# aecho.net
KiCad netlist of a schematic drawn in EAGLE
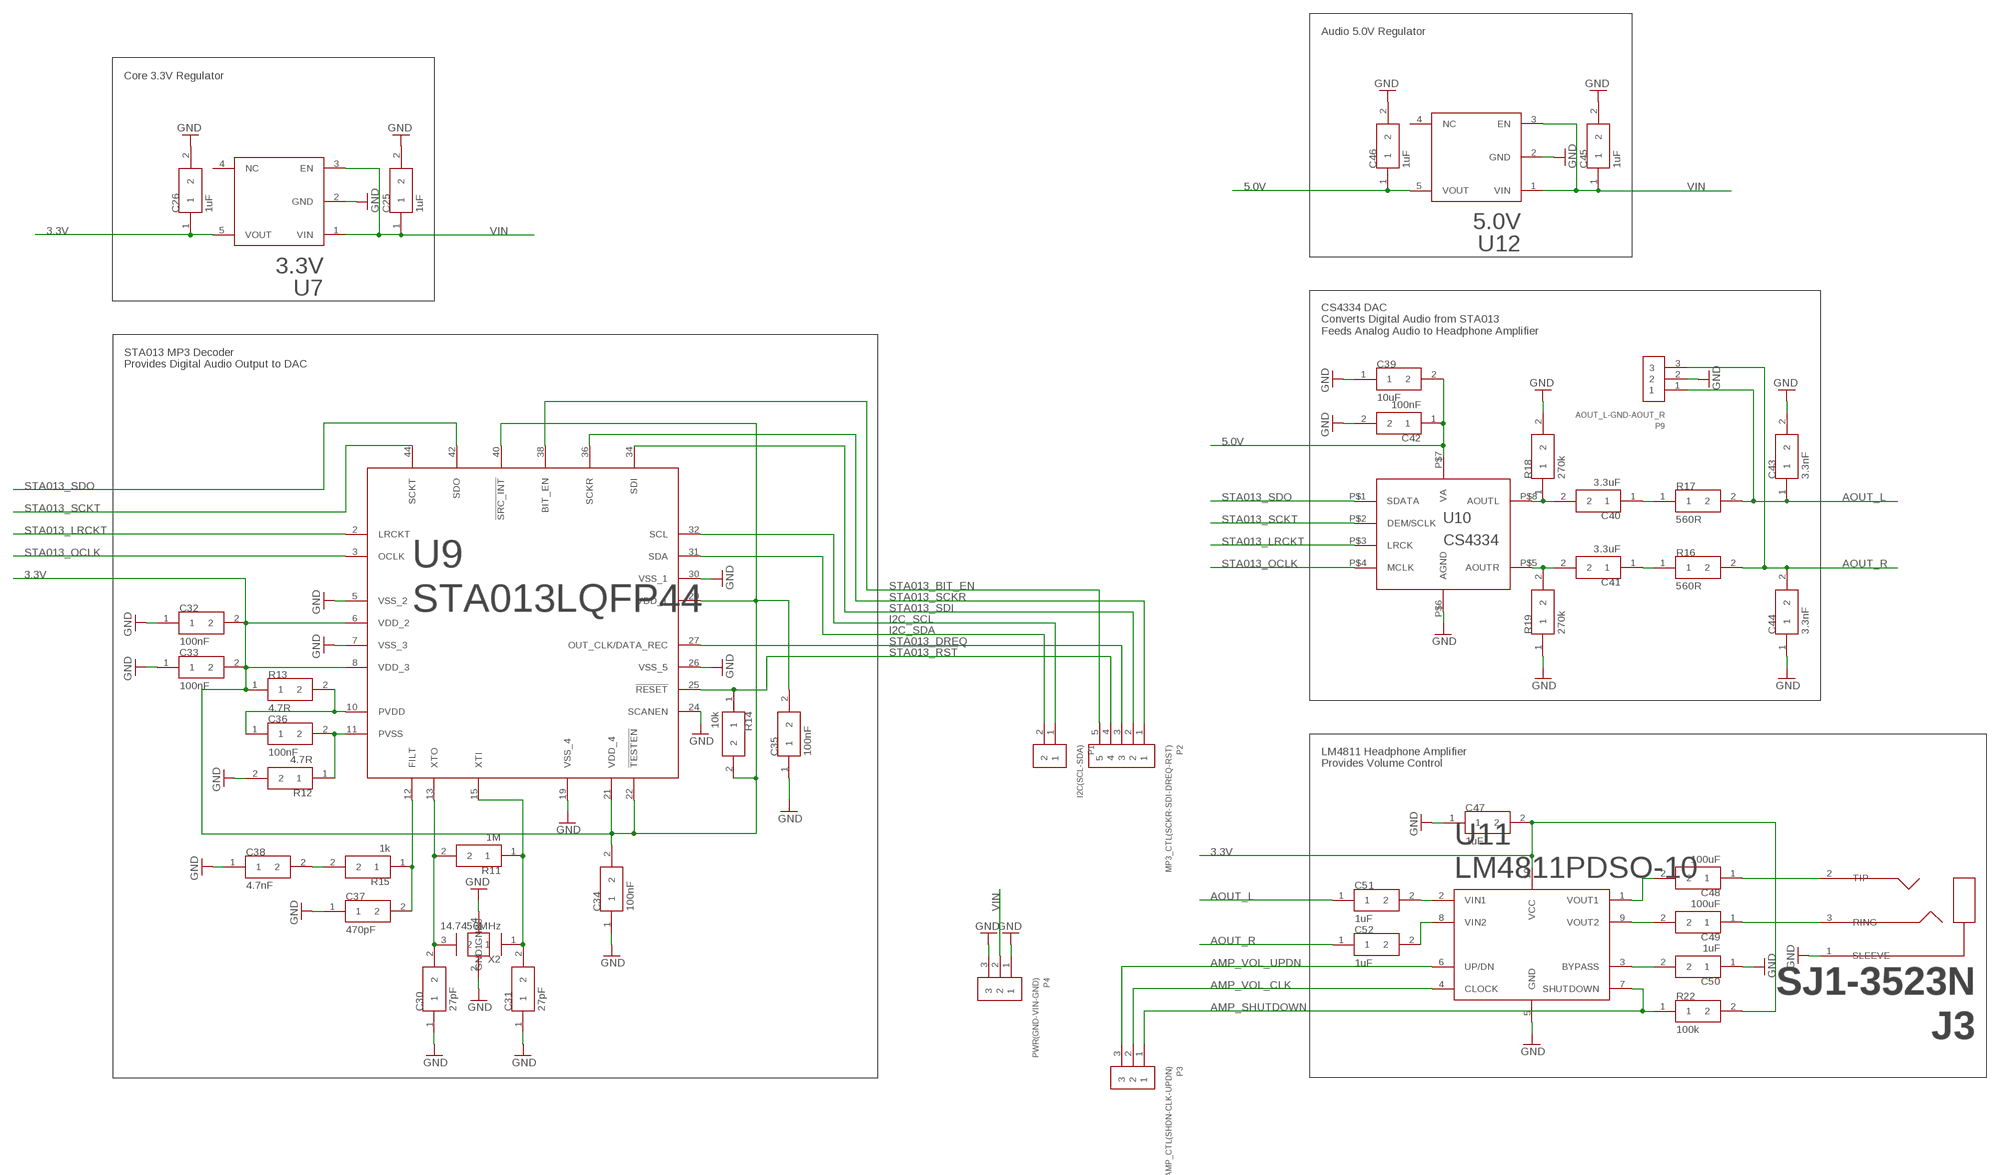
[diagram p0: schematic, sheet 1]

(export (version "E")
  (design (tool "Eeschema 10.0.6"))
  (components
    (comp (ref "C25")
      (value "1uF")
      (footprint "eagle-import:0805")
      (libsource (lib "eagle-import") (part "CAP0805"))
    )
    (comp (ref "C26")
      (value "1uF")
      (footprint "eagle-import:0805")
      (libsource (lib "eagle-import") (part "CAP0805"))
    )
    (comp (ref "C30")
      (value "27pF")
      (footprint "eagle-import:0805")
      (libsource (lib "eagle-import") (part "CAP0805"))
    )
    (comp (ref "C31")
      (value "27pF")
      (footprint "eagle-import:0805")
      (libsource (lib "eagle-import") (part "CAP0805"))
    )
    (comp (ref "C32")
      (value "100nF")
      (footprint "eagle-import:0805")
      (libsource (lib "eagle-import") (part "CAP0805"))
    )
    (comp (ref "C33")
      (value "100nF")
      (footprint "eagle-import:0805")
      (libsource (lib "eagle-import") (part "CAP0805"))
    )
    (comp (ref "C34")
      (value "100nF")
      (footprint "eagle-import:0805")
      (libsource (lib "eagle-import") (part "CAP0805"))
    )
    (comp (ref "C35")
      (value "100nF")
      (footprint "eagle-import:0805")
      (libsource (lib "eagle-import") (part "CAP0805"))
    )
    (comp (ref "C36")
      (value "100nF")
      (footprint "eagle-import:0805")
      (libsource (lib "eagle-import") (part "CAP0805"))
    )
    (comp (ref "C37")
      (value "470pF")
      (footprint "eagle-import:0805")
      (libsource (lib "eagle-import") (part "CAP0805"))
    )
    (comp (ref "C38")
      (value "4.7nF")
      (footprint "eagle-import:0805")
      (libsource (lib "eagle-import") (part "CAP0805"))
    )
    (comp (ref "C39")
      (value "10uF")
      (footprint "eagle-import:0805")
      (libsource (lib "eagle-import") (part "CAP0805"))
    )
    (comp (ref "C40")
      (value "3.3uF")
      (footprint "eagle-import:0805")
      (libsource (lib "eagle-import") (part "CAP0805"))
    )
    (comp (ref "C41")
      (value "3.3uF")
      (footprint "eagle-import:0805")
      (libsource (lib "eagle-import") (part "CAP0805"))
    )
    (comp (ref "C42")
      (value "100nF")
      (footprint "eagle-import:0805")
      (libsource (lib "eagle-import") (part "CAP0805"))
    )
    (comp (ref "C43")
      (value "3.3nF")
      (footprint "eagle-import:0805")
      (libsource (lib "eagle-import") (part "CAP0805"))
    )
    (comp (ref "C44")
      (value "3.3nF")
      (footprint "eagle-import:0805")
      (libsource (lib "eagle-import") (part "CAP0805"))
    )
    (comp (ref "C45")
      (value "1uF")
      (footprint "eagle-import:0805")
      (libsource (lib "eagle-import") (part "CAP0805"))
    )
    (comp (ref "C46")
      (value "1uF")
      (footprint "eagle-import:0805")
      (libsource (lib "eagle-import") (part "CAP0805"))
    )
    (comp (ref "C47")
      (value "1uF")
      (footprint "eagle-import:0805")
      (libsource (lib "eagle-import") (part "CAP0805"))
    )
    (comp (ref "C48")
      (value "100uF")
      (footprint "eagle-import:1210")
      (libsource (lib "eagle-import") (part "CAP1210"))
    )
    (comp (ref "C49")
      (value "100uF")
      (footprint "eagle-import:1210")
      (libsource (lib "eagle-import") (part "CAP1210"))
    )
    (comp (ref "C50")
      (value "1uF")
      (footprint "eagle-import:0805")
      (libsource (lib "eagle-import") (part "CAP0805"))
    )
    (comp (ref "C51")
      (value "1uF")
      (footprint "eagle-import:0805")
      (libsource (lib "eagle-import") (part "CAP0805"))
    )
    (comp (ref "C52")
      (value "1uF")
      (footprint "eagle-import:0805")
      (libsource (lib "eagle-import") (part "CAP0805"))
    )
    (comp (ref "J3")
      (value "SJ1-3523N")
      (footprint "eagle-import:SJ1-352XN")
      (libsource (lib "eagle-import") (part "SJ1-3523N"))
    )
    (comp (ref "P1")
      (value "I2C(SCL-SDA)")
      (footprint "eagle-import:PIN_2")
      (libsource (lib "eagle-import") (part "PIN_2"))
    )
    (comp (ref "P2")
      (value "MP3_CTL(SCKR-SDI-DREQ-RST)")
      (footprint "eagle-import:PIN_5")
      (libsource (lib "eagle-import") (part "PIN_5"))
    )
    (comp (ref "P3")
      (value "AMP_CTL(SHDN-CLK-UPDN)")
      (footprint "eagle-import:PIN_3")
      (libsource (lib "eagle-import") (part "PIN_3"))
    )
    (comp (ref "P4")
      (value "PWR(GND-VIN-GND)")
      (footprint "eagle-import:PIN_3")
      (libsource (lib "eagle-import") (part "PIN_3"))
    )
    (comp (ref "P9")
      (value "AOUT_L-GND-AOUT_R")
      (footprint "eagle-import:PIN_3")
      (libsource (lib "eagle-import") (part "PIN_3"))
    )
    (comp (ref "R11")
      (value "1M")
      (footprint "eagle-import:0805")
      (libsource (lib "eagle-import") (part "RES0805"))
    )
    (comp (ref "R12")
      (value "4.7R")
      (footprint "eagle-import:0805")
      (libsource (lib "eagle-import") (part "RES0805"))
    )
    (comp (ref "R13")
      (value "4.7R")
      (footprint "eagle-import:0805")
      (libsource (lib "eagle-import") (part "RES0805"))
    )
    (comp (ref "R14")
      (value "10k")
      (footprint "eagle-import:0805")
      (libsource (lib "eagle-import") (part "RES0805"))
    )
    (comp (ref "R15")
      (value "1k")
      (footprint "eagle-import:0805")
      (libsource (lib "eagle-import") (part "RES0805"))
    )
    (comp (ref "R16")
      (value "560R")
      (footprint "eagle-import:0805")
      (libsource (lib "eagle-import") (part "RES0805"))
    )
    (comp (ref "R17")
      (value "560R")
      (footprint "eagle-import:0805")
      (libsource (lib "eagle-import") (part "RES0805"))
    )
    (comp (ref "R18")
      (value "270k")
      (footprint "eagle-import:0805")
      (libsource (lib "eagle-import") (part "RES0805"))
    )
    (comp (ref "R19")
      (value "270k")
      (footprint "eagle-import:0805")
      (libsource (lib "eagle-import") (part "RES0805"))
    )
    (comp (ref "R22")
      (value "100k")
      (footprint "eagle-import:0805")
      (libsource (lib "eagle-import") (part "RES0805"))
    )
    (comp (ref "U7")
      (value "3.3V")
      (footprint "eagle-import:SOT23-5")
      (libsource (lib "eagle-import") (part "LP3985SOT23-5"))
    )
    (comp (ref "U9")
      (value "STA013LQFP44")
      (footprint "eagle-import:QFP44")
      (libsource (lib "eagle-import") (part "STA013LQFP44"))
    )
    (comp (ref "U10")
      (value "CS4334")
      (footprint "eagle-import:SO8")
      (libsource (lib "eagle-import") (part "CS4334"))
    )
    (comp (ref "U11")
      (value "LM4811PDSO-10")
      (footprint "eagle-import:PDSO-10")
      (libsource (lib "eagle-import") (part "LM4811PDSO-10"))
    )
    (comp (ref "U12")
      (value "5.0V")
      (footprint "eagle-import:SOT23-5")
      (libsource (lib "eagle-import") (part "LP3985SOT23-5"))
    )
    (comp (ref "X2")
      (value "14.7456MHz")
      (footprint "eagle-import:XTAL_3225")
      (libsource (lib "eagle-import") (part "XTAL_GNDSMD_3225"))
    )
  )
  (nets
    (net (code "1") (name "/3.3V") (class "Default")
      (node (ref "C26") (pin "1") (pinfunction "1_1") (pintype "bidirectional"))
      (node (ref "C32") (pin "2") (pinfunction "2_2") (pintype "bidirectional"))
      (node (ref "C33") (pin "2") (pinfunction "2_2") (pintype "bidirectional"))
      (node (ref "C34") (pin "2") (pinfunction "2_2") (pintype "bidirectional"))
      (node (ref "C35") (pin "2") (pinfunction "2_2") (pintype "bidirectional"))
      (node (ref "C47") (pin "2") (pinfunction "2_2") (pintype "bidirectional"))
      (node (ref "R13") (pin "1") (pinfunction "1_1") (pintype "bidirectional"))
      (node (ref "R14") (pin "2") (pinfunction "2_2") (pintype "bidirectional"))
      (node (ref "R22") (pin "2") (pinfunction "2_2") (pintype "bidirectional"))
      (node (ref "U11") (pin "10") (pinfunction "VCC_10") (pintype "bidirectional"))
      (node (ref "U7") (pin "5") (pinfunction "VOUT_5") (pintype "bidirectional"))
      (node (ref "U9") (pin "21") (pinfunction "VDD_4_21") (pintype "bidirectional"))
      (node (ref "U9") (pin "22") (pinfunction "~{TESTEN}_22") (pintype "bidirectional"))
      (node (ref "U9") (pin "29") (pinfunction "VDD_1_29") (pintype "bidirectional"))
      (node (ref "U9") (pin "40") (pinfunction "~{SRC_INT}_40") (pintype "bidirectional"))
      (node (ref "U9") (pin "6") (pinfunction "VDD_2_6") (pintype "bidirectional"))
      (node (ref "U9") (pin "8") (pinfunction "VDD_3_8") (pintype "bidirectional"))
    )
    (net (code "2") (name "/5.0V") (class "Default")
      (node (ref "C39") (pin "2") (pinfunction "2_2") (pintype "bidirectional"))
      (node (ref "C42") (pin "1") (pinfunction "1_1") (pintype "bidirectional"))
      (node (ref "C46") (pin "1") (pinfunction "1_1") (pintype "bidirectional"))
      (node (ref "U10") (pin "P$7") (pinfunction "VA_P$7") (pintype "bidirectional"))
      (node (ref "U12") (pin "5") (pinfunction "VOUT_5") (pintype "bidirectional"))
    )
    (net (code "3") (name "/AMP_SHUTDOWN") (class "Default")
      (node (ref "P3") (pin "1") (pinfunction "1_1") (pintype "bidirectional"))
      (node (ref "R22") (pin "1") (pinfunction "1_1") (pintype "bidirectional"))
      (node (ref "U11") (pin "7") (pinfunction "SHUTDOWN_7") (pintype "bidirectional"))
    )
    (net (code "4") (name "/AMP_VOL_CLK") (class "Default")
      (node (ref "P3") (pin "2") (pinfunction "2_2") (pintype "bidirectional"))
      (node (ref "U11") (pin "4") (pinfunction "CLOCK_4") (pintype "bidirectional"))
    )
    (net (code "5") (name "/AMP_VOL_UPDN") (class "Default")
      (node (ref "P3") (pin "3") (pinfunction "3_3") (pintype "bidirectional"))
      (node (ref "U11") (pin "6") (pinfunction "UP/DN_6") (pintype "bidirectional"))
    )
    (net (code "6") (name "/AOUT_L") (class "Default")
      (node (ref "C43") (pin "1") (pinfunction "1_1") (pintype "bidirectional"))
      (node (ref "C51") (pin "1") (pinfunction "1_1") (pintype "bidirectional"))
      (node (ref "P9") (pin "1") (pinfunction "1_1") (pintype "bidirectional"))
      (node (ref "R17") (pin "2") (pinfunction "2_2") (pintype "bidirectional"))
    )
    (net (code "7") (name "/AOUT_R") (class "Default")
      (node (ref "C44") (pin "2") (pinfunction "2_2") (pintype "bidirectional"))
      (node (ref "C52") (pin "1") (pinfunction "1_1") (pintype "bidirectional"))
      (node (ref "P9") (pin "3") (pinfunction "3_3") (pintype "bidirectional"))
      (node (ref "R16") (pin "2") (pinfunction "2_2") (pintype "bidirectional"))
    )
    (net (code "8") (name "/I2C_SCL") (class "Default")
      (node (ref "P1") (pin "1") (pinfunction "1_1") (pintype "bidirectional"))
      (node (ref "U9") (pin "32") (pinfunction "SCL_32") (pintype "bidirectional"))
    )
    (net (code "9") (name "/I2C_SDA") (class "Default")
      (node (ref "P1") (pin "2") (pinfunction "2_2") (pintype "bidirectional"))
      (node (ref "U9") (pin "31") (pinfunction "SDA_31") (pintype "bidirectional"))
    )
    (net (code "10") (name "/STA013_BIT_EN") (class "Default")
      (node (ref "P2") (pin "5") (pinfunction "5_5") (pintype "bidirectional"))
      (node (ref "U9") (pin "38") (pinfunction "BIT_EN_38") (pintype "bidirectional"))
    )
    (net (code "11") (name "/STA013_DREQ") (class "Default")
      (node (ref "P2") (pin "3") (pinfunction "3_3") (pintype "bidirectional"))
      (node (ref "U9") (pin "27") (pinfunction "OUT_CLK/DATA_REC_27") (pintype "bidirectional"))
    )
    (net (code "12") (name "/STA013_LRCKT") (class "Default")
      (node (ref "U10") (pin "P$3") (pinfunction "LRCK_P$3") (pintype "bidirectional"))
      (node (ref "U9") (pin "2") (pinfunction "LRCKT_2") (pintype "bidirectional"))
    )
    (net (code "13") (name "/STA013_OCLK") (class "Default")
      (node (ref "U10") (pin "P$4") (pinfunction "MCLK_P$4") (pintype "bidirectional"))
      (node (ref "U9") (pin "3") (pinfunction "OCLK_3") (pintype "bidirectional"))
    )
    (net (code "14") (name "/STA013_SCKR") (class "Default")
      (node (ref "P2") (pin "1") (pinfunction "1_1") (pintype "bidirectional"))
      (node (ref "U9") (pin "36") (pinfunction "SCKR_36") (pintype "bidirectional"))
    )
    (net (code "15") (name "/STA013_SCKT") (class "Default")
      (node (ref "U10") (pin "P$2") (pinfunction "DEM/SCLK_P$2") (pintype "bidirectional"))
      (node (ref "U9") (pin "44") (pinfunction "SCKT_44") (pintype "bidirectional"))
    )
    (net (code "16") (name "/STA013_SDI") (class "Default")
      (node (ref "P2") (pin "2") (pinfunction "2_2") (pintype "bidirectional"))
      (node (ref "U9") (pin "34") (pinfunction "SDI_34") (pintype "bidirectional"))
    )
    (net (code "17") (name "/STA013_SDO") (class "Default")
      (node (ref "U10") (pin "P$1") (pinfunction "SDATA_P$1") (pintype "bidirectional"))
      (node (ref "U9") (pin "42") (pinfunction "SDO_42") (pintype "bidirectional"))
    )
    (net (code "18") (name "/VIN") (class "Default")
      (node (ref "C25") (pin "1") (pinfunction "1_1") (pintype "bidirectional"))
      (node (ref "C45") (pin "1") (pinfunction "1_1") (pintype "bidirectional"))
      (node (ref "P4") (pin "2") (pinfunction "2_2") (pintype "bidirectional"))
      (node (ref "U12") (pin "1") (pinfunction "VIN_1") (pintype "bidirectional"))
      (node (ref "U12") (pin "3") (pinfunction "EN_3") (pintype "bidirectional"))
      (node (ref "U7") (pin "1") (pinfunction "VIN_1") (pintype "bidirectional"))
      (node (ref "U7") (pin "3") (pinfunction "EN_3") (pintype "bidirectional"))
    )
    (net (code "19") (name "/~{STA013_RST}") (class "Default")
      (node (ref "P2") (pin "4") (pinfunction "4_4") (pintype "bidirectional"))
      (node (ref "R14") (pin "1") (pinfunction "1_1") (pintype "bidirectional"))
      (node (ref "U9") (pin "25") (pinfunction "~{RESET}_25") (pintype "bidirectional"))
    )
    (net (code "20") (name "GND") (class "Default")
      (node (ref "C25") (pin "2") (pinfunction "2_2") (pintype "bidirectional"))
      (node (ref "C26") (pin "2") (pinfunction "2_2") (pintype "bidirectional"))
      (node (ref "C30") (pin "1") (pinfunction "1_1") (pintype "bidirectional"))
      (node (ref "C31") (pin "1") (pinfunction "1_1") (pintype "bidirectional"))
      (node (ref "C32") (pin "1") (pinfunction "1_1") (pintype "bidirectional"))
      (node (ref "C33") (pin "1") (pinfunction "1_1") (pintype "bidirectional"))
      (node (ref "C34") (pin "1") (pinfunction "1_1") (pintype "bidirectional"))
      (node (ref "C35") (pin "1") (pinfunction "1_1") (pintype "bidirectional"))
      (node (ref "C37") (pin "1") (pinfunction "1_1") (pintype "bidirectional"))
      (node (ref "C38") (pin "1") (pinfunction "1_1") (pintype "bidirectional"))
      (node (ref "C39") (pin "1") (pinfunction "1_1") (pintype "bidirectional"))
      (node (ref "C42") (pin "2") (pinfunction "2_2") (pintype "bidirectional"))
      (node (ref "C43") (pin "2") (pinfunction "2_2") (pintype "bidirectional"))
      (node (ref "C44") (pin "1") (pinfunction "1_1") (pintype "bidirectional"))
      (node (ref "C45") (pin "2") (pinfunction "2_2") (pintype "bidirectional"))
      (node (ref "C46") (pin "2") (pinfunction "2_2") (pintype "bidirectional"))
      (node (ref "C47") (pin "1") (pinfunction "1_1") (pintype "bidirectional"))
      (node (ref "C50") (pin "1") (pinfunction "1_1") (pintype "bidirectional"))
      (node (ref "J3") (pin "1") (pinfunction "SLEEVE_1") (pintype "bidirectional"))
      (node (ref "P4") (pin "1") (pinfunction "1_1") (pintype "bidirectional"))
      (node (ref "P4") (pin "3") (pinfunction "3_3") (pintype "bidirectional"))
      (node (ref "P9") (pin "2") (pinfunction "2_2") (pintype "bidirectional"))
      (node (ref "R12") (pin "2") (pinfunction "2_2") (pintype "bidirectional"))
      (node (ref "R18") (pin "2") (pinfunction "2_2") (pintype "bidirectional"))
      (node (ref "R19") (pin "1") (pinfunction "1_1") (pintype "bidirectional"))
      (node (ref "U10") (pin "P$6") (pinfunction "AGND_P$6") (pintype "bidirectional"))
      (node (ref "U11") (pin "5") (pinfunction "GND_5") (pintype "bidirectional"))
      (node (ref "U12") (pin "2") (pinfunction "GND_2") (pintype "bidirectional"))
      (node (ref "U7") (pin "2") (pinfunction "GND_2") (pintype "bidirectional"))
      (node (ref "U9") (pin "19") (pinfunction "VSS_4_19") (pintype "bidirectional"))
      (node (ref "U9") (pin "24") (pinfunction "SCANEN_24") (pintype "bidirectional"))
      (node (ref "U9") (pin "26") (pinfunction "VSS_5_26") (pintype "bidirectional"))
      (node (ref "U9") (pin "30") (pinfunction "VSS_1_30") (pintype "bidirectional"))
      (node (ref "U9") (pin "5") (pinfunction "VSS_2_5") (pintype "bidirectional"))
      (node (ref "U9") (pin "7") (pinfunction "VSS_3_7") (pintype "bidirectional"))
      (node (ref "X2") (pin "2") (pinfunction "GND0_2") (pintype "bidirectional"))
      (node (ref "X2") (pin "4") (pinfunction "GND1_4") (pintype "bidirectional"))
    )
    (net (code "21") (name "Net-(C38-Pad2)") (class "Default")
      (node (ref "C38") (pin "2") (pinfunction "2_2") (pintype "bidirectional"))
      (node (ref "R15") (pin "2") (pinfunction "2_2") (pintype "bidirectional"))
    )
    (net (code "22") (name "Net-(C40-Pad1)") (class "Default")
      (node (ref "C40") (pin "1") (pinfunction "1_1") (pintype "bidirectional"))
      (node (ref "R17") (pin "1") (pinfunction "1_1") (pintype "bidirectional"))
    )
    (net (code "23") (name "Net-(C41-Pad1)") (class "Default")
      (node (ref "C41") (pin "1") (pinfunction "1_1") (pintype "bidirectional"))
      (node (ref "R16") (pin "1") (pinfunction "1_1") (pintype "bidirectional"))
    )
    (net (code "24") (name "Net-(J3-RING)") (class "Default")
      (node (ref "C49") (pin "1") (pinfunction "1_1") (pintype "bidirectional"))
      (node (ref "J3") (pin "3") (pinfunction "RING_3") (pintype "bidirectional"))
    )
    (net (code "25") (name "Net-(J3-TIP)") (class "Default")
      (node (ref "C48") (pin "1") (pinfunction "1_1") (pintype "bidirectional"))
      (node (ref "J3") (pin "2") (pinfunction "TIP_2") (pintype "bidirectional"))
    )
    (net (code "26") (name "Net-(U9-FILT)") (class "Default")
      (node (ref "C37") (pin "2") (pinfunction "2_2") (pintype "bidirectional"))
      (node (ref "R15") (pin "1") (pinfunction "1_1") (pintype "bidirectional"))
      (node (ref "U9") (pin "12") (pinfunction "FILT_12") (pintype "bidirectional"))
    )
    (net (code "27") (name "Net-(U9-PVDD)") (class "Default")
      (node (ref "C36") (pin "1") (pinfunction "1_1") (pintype "bidirectional"))
      (node (ref "R13") (pin "2") (pinfunction "2_2") (pintype "bidirectional"))
      (node (ref "U9") (pin "10") (pinfunction "PVDD_10") (pintype "bidirectional"))
    )
    (net (code "28") (name "Net-(U9-PVSS)") (class "Default")
      (node (ref "C36") (pin "2") (pinfunction "2_2") (pintype "bidirectional"))
      (node (ref "R12") (pin "1") (pinfunction "1_1") (pintype "bidirectional"))
      (node (ref "U9") (pin "11") (pinfunction "PVSS_11") (pintype "bidirectional"))
    )
    (net (code "29") (name "Net-(U9-XTI)") (class "Default")
      (node (ref "C31") (pin "2") (pinfunction "2_2") (pintype "bidirectional"))
      (node (ref "R11") (pin "1") (pinfunction "1_1") (pintype "bidirectional"))
      (node (ref "U9") (pin "15") (pinfunction "XTI_15") (pintype "bidirectional"))
      (node (ref "X2") (pin "1") (pinfunction "1_1") (pintype "bidirectional"))
    )
    (net (code "30") (name "Net-(U9-XTO)") (class "Default")
      (node (ref "C30") (pin "2") (pinfunction "2_2") (pintype "bidirectional"))
      (node (ref "R11") (pin "2") (pinfunction "2_2") (pintype "bidirectional"))
      (node (ref "U9") (pin "13") (pinfunction "XTO_13") (pintype "bidirectional"))
      (node (ref "X2") (pin "3") (pinfunction "2_3") (pintype "bidirectional"))
    )
    (net (code "31") (name "Net-(U10-AOUTL)") (class "Default")
      (node (ref "C40") (pin "2") (pinfunction "2_2") (pintype "bidirectional"))
      (node (ref "R18") (pin "1") (pinfunction "1_1") (pintype "bidirectional"))
      (node (ref "U10") (pin "P$8") (pinfunction "AOUTL_P$8") (pintype "bidirectional"))
    )
    (net (code "32") (name "Net-(U10-AOUTR)") (class "Default")
      (node (ref "C41") (pin "2") (pinfunction "2_2") (pintype "bidirectional"))
      (node (ref "R19") (pin "2") (pinfunction "2_2") (pintype "bidirectional"))
      (node (ref "U10") (pin "P$5") (pinfunction "AOUTR_P$5") (pintype "bidirectional"))
    )
    (net (code "33") (name "Net-(U11-BYPASS)") (class "Default")
      (node (ref "C50") (pin "2") (pinfunction "2_2") (pintype "bidirectional"))
      (node (ref "U11") (pin "3") (pinfunction "BYPASS_3") (pintype "bidirectional"))
    )
    (net (code "34") (name "Net-(U11-VIN1)") (class "Default")
      (node (ref "C51") (pin "2") (pinfunction "2_2") (pintype "bidirectional"))
      (node (ref "U11") (pin "2") (pinfunction "VIN1_2") (pintype "bidirectional"))
    )
    (net (code "35") (name "Net-(U11-VIN2)") (class "Default")
      (node (ref "C52") (pin "2") (pinfunction "2_2") (pintype "bidirectional"))
      (node (ref "U11") (pin "8") (pinfunction "VIN2_8") (pintype "bidirectional"))
    )
    (net (code "36") (name "Net-(U11-VOUT1)") (class "Default")
      (node (ref "C48") (pin "2") (pinfunction "2_2") (pintype "bidirectional"))
      (node (ref "U11") (pin "1") (pinfunction "VOUT1_1") (pintype "bidirectional"))
    )
    (net (code "37") (name "Net-(U11-VOUT2)") (class "Default")
      (node (ref "C49") (pin "2") (pinfunction "2_2") (pintype "bidirectional"))
      (node (ref "U11") (pin "9") (pinfunction "VOUT2_9") (pintype "bidirectional"))
    )
    (net (code "38") (name "unconnected-(U7-NC-Pad4)") (class "Default")
      (node (ref "U7") (pin "4") (pinfunction "NC_4") (pintype "bidirectional"))
    )
    (net (code "39") (name "unconnected-(U12-NC-Pad4)") (class "Default")
      (node (ref "U12") (pin "4") (pinfunction "NC_4") (pintype "bidirectional"))
    )
  )
)
